# mapleSDuino-V0_1_012-eagle7.net
KiCad netlist of a schematic drawn in EAGLE
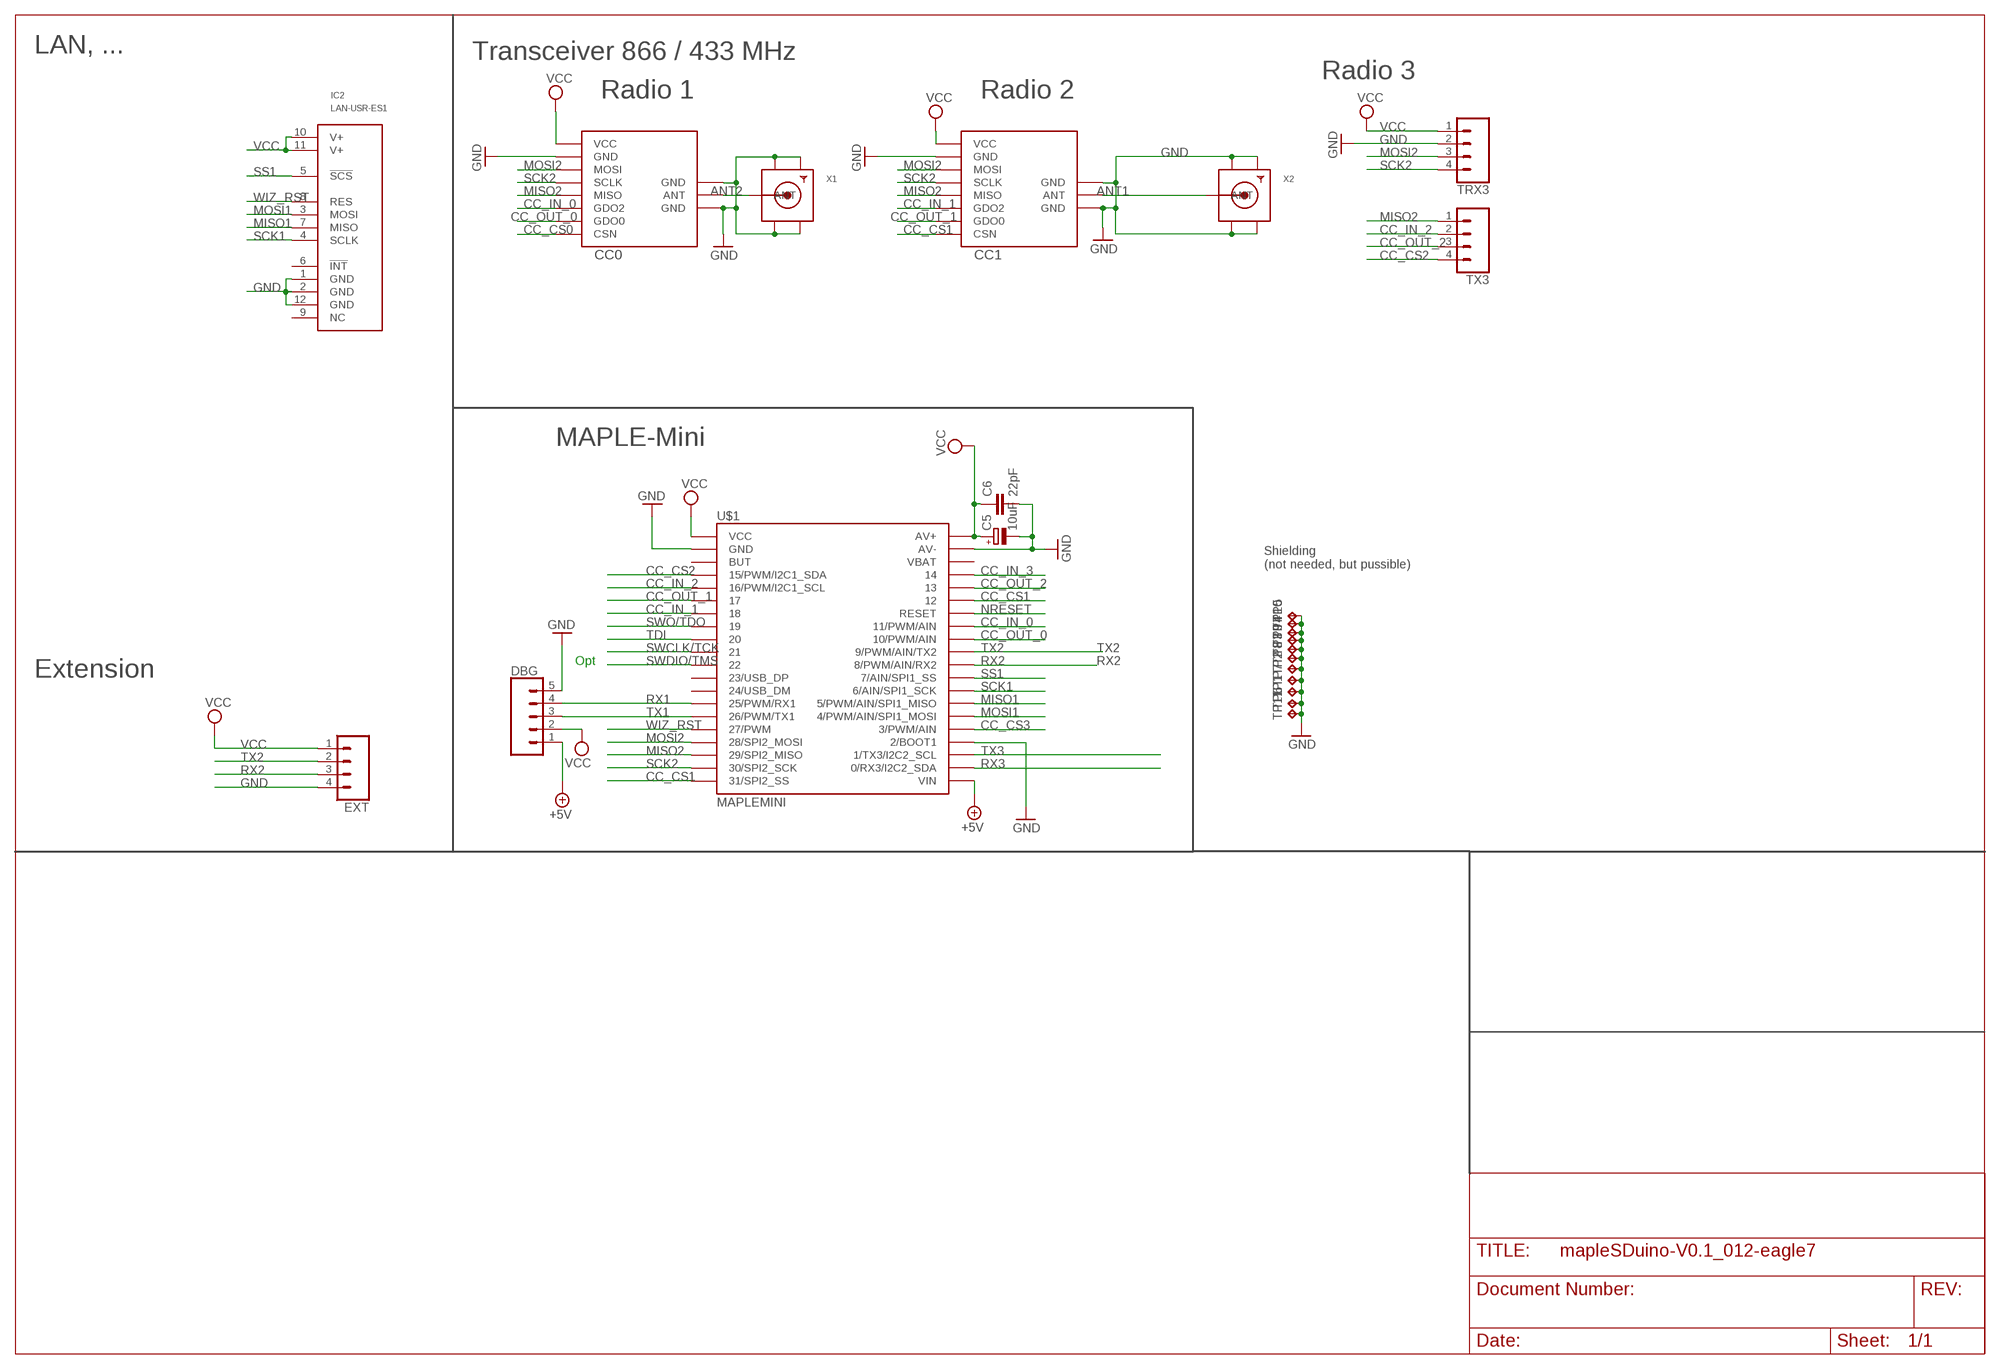
[diagram p0: schematic, sheet 1]

(export (version "E")
  (design (tool "Eeschema 10.0.6"))
  (components
    (comp (ref "C5")
      (value "10uF")
      (footprint "eagle-import:R_2012-12W")
      (libsource (lib "eagle-import") (part "CPOL-EUR/2012-12W"))
    )
    (comp (ref "C6")
      (value "22pF")
      (footprint "eagle-import:C0805")
      (libsource (lib "eagle-import") (part "C-EUC0805"))
    )
    (comp (ref "CC0")
      (value "CC1101")
      (footprint "eagle-import:CC1101_MODULE1_SMD")
      (libsource (lib "eagle-import") (part "CC1101_MODULE1SMD"))
    )
    (comp (ref "CC1")
      (value "CC1101_MODULE1SMD")
      (footprint "eagle-import:CC1101_MODULE1_SMD")
      (libsource (lib "eagle-import") (part "CC1101_MODULE1SMD"))
    )
    (comp (ref "DBG")
      (value "CONN_05LOCK")
      (footprint "eagle-import:1X05_LOCK")
      (libsource (lib "eagle-import") (part "CONN_05LOCK"))
    )
    (comp (ref "EXT")
      (value "CONN_04PTH")
      (footprint "eagle-import:1X04")
      (libsource (lib "eagle-import") (part "CONN_04PTH"))
    )
    (comp (ref "IC2")
      (value "LAN-USR-ES1")
      (footprint "eagle-import:USR-ES1")
      (libsource (lib "eagle-import") (part "LAN-USR-ES1"))
    )
    (comp (ref "TP1")
      (value "TPTP06SQ")
      (footprint "eagle-import:TP06SQ")
      (libsource (lib "eagle-import") (part "TPTP06SQ"))
    )
    (comp (ref "TP2")
      (value "TPTP06SQ")
      (footprint "eagle-import:TP06SQ")
      (libsource (lib "eagle-import") (part "TPTP06SQ"))
    )
    (comp (ref "TP3")
      (value "TPTP06SQ")
      (footprint "eagle-import:TP06SQ")
      (libsource (lib "eagle-import") (part "TPTP06SQ"))
    )
    (comp (ref "TP4")
      (value "TPTP06SQ")
      (footprint "eagle-import:TP06SQ")
      (libsource (lib "eagle-import") (part "TPTP06SQ"))
    )
    (comp (ref "TP5")
      (value "TPTP06SQ")
      (footprint "eagle-import:TP06SQ")
      (libsource (lib "eagle-import") (part "TPTP06SQ"))
    )
    (comp (ref "TP6")
      (value "TPTP06SQ")
      (footprint "eagle-import:TP06SQ")
      (libsource (lib "eagle-import") (part "TPTP06SQ"))
    )
    (comp (ref "TP7")
      (value "TPTP06SQ")
      (footprint "eagle-import:TP06SQ")
      (libsource (lib "eagle-import") (part "TPTP06SQ"))
    )
    (comp (ref "TP8")
      (value "TPTP06SQ")
      (footprint "eagle-import:TP06SQ")
      (libsource (lib "eagle-import") (part "TPTP06SQ"))
    )
    (comp (ref "TP9")
      (value "TPTP06SQ")
      (footprint "eagle-import:TP06SQ")
      (libsource (lib "eagle-import") (part "TPTP06SQ"))
    )
    (comp (ref "TP10")
      (value "TPTP06SQ")
      (footprint "eagle-import:TP06SQ")
      (libsource (lib "eagle-import") (part "TPTP06SQ"))
    )
    (comp (ref "TP11")
      (value "TPTP06SQ")
      (footprint "eagle-import:TP06SQ")
      (libsource (lib "eagle-import") (part "TPTP06SQ"))
    )
    (comp (ref "TRX3")
      (value "CONN_04PTH")
      (footprint "eagle-import:1X04")
      (libsource (lib "eagle-import") (part "CONN_04PTH"))
    )
    (comp (ref "TX3")
      (value "CONN_04PTH")
      (footprint "eagle-import:1X04")
      (libsource (lib "eagle-import") (part "CONN_04PTH"))
    )
    (comp (ref "U$1")
      (value "MAPLEMINI")
      (footprint "eagle-import:20-DIP")
      (libsource (lib "eagle-import") (part "MAPLEMINI"))
    )
    (comp (ref "X1")
      (value "SMACONNECTOR_EDGE")
      (footprint "eagle-import:SMA_EDGELAUNCH")
      (libsource (lib "eagle-import") (part "SMACONNECTOR_EDGE"))
    )
    (comp (ref "X2")
      (value "SMACONNECTOR_EDGE")
      (footprint "eagle-import:SMA_EDGELAUNCH")
      (libsource (lib "eagle-import") (part "SMACONNECTOR_EDGE"))
    )
  )
  (nets
    (net (code "1") (name "+5V") (class "Default")
      (node (ref "DBG") (pin "1") (pinfunction "1_1") (pintype "passive"))
      (node (ref "U$1") (pin "21") (pinfunction "VIN_21") (pintype "bidirectional"))
    )
    (net (code "2") (name "/ANT1") (class "Default")
      (node (ref "CC1") (pin "ANT") (pinfunction "ANT_ANT") (pintype "output"))
      (node (ref "X2") (pin "P") (pinfunction "ANT_P") (pintype "bidirectional"))
    )
    (net (code "3") (name "/ANT2") (class "Default")
      (node (ref "CC0") (pin "ANT") (pinfunction "ANT_ANT") (pintype "output"))
      (node (ref "X1") (pin "P") (pinfunction "ANT_P") (pintype "bidirectional"))
    )
    (net (code "4") (name "/CC_CS0") (class "Default")
      (node (ref "CC0") (pin "CSN") (pinfunction "CSN_CSN") (pintype "bidirectional"))
    )
    (net (code "5") (name "/CC_CS1") (class "Default")
      (node (ref "CC1") (pin "CSN") (pinfunction "CSN_CSN") (pintype "bidirectional"))
      (node (ref "U$1") (pin "20") (pinfunction "31/SPI2_SS_20") (pintype "bidirectional"))
      (node (ref "U$1") (pin "35") (pinfunction "12_35") (pintype "bidirectional"))
    )
    (net (code "6") (name "/CC_CS2") (class "Default")
      (node (ref "TX3") (pin "4") (pinfunction "4_4") (pintype "passive"))
      (node (ref "U$1") (pin "4") (pinfunction "15/PWM/I2C1_SDA_4") (pintype "bidirectional"))
    )
    (net (code "7") (name "/CC_CS3") (class "Default")
      (node (ref "U$1") (pin "25") (pinfunction "3/PWM/AIN_25") (pintype "bidirectional"))
    )
    (net (code "8") (name "/CC_IN_0") (class "Default")
      (node (ref "CC0") (pin "GDO2") (pinfunction "GDO2_GDO2") (pintype "bidirectional"))
      (node (ref "U$1") (pin "33") (pinfunction "11/PWM/AIN_33") (pintype "bidirectional"))
    )
    (net (code "9") (name "/CC_IN_1") (class "Default")
      (node (ref "CC1") (pin "GDO2") (pinfunction "GDO2_GDO2") (pintype "bidirectional"))
      (node (ref "U$1") (pin "7") (pinfunction "18_7") (pintype "bidirectional"))
    )
    (net (code "10") (name "/CC_IN_2") (class "Default")
      (node (ref "TX3") (pin "2") (pinfunction "2_2") (pintype "passive"))
      (node (ref "U$1") (pin "5") (pinfunction "16/PWM/I2C1_SCL_5") (pintype "bidirectional"))
    )
    (net (code "11") (name "/CC_IN_3") (class "Default")
      (node (ref "U$1") (pin "37") (pinfunction "14_37") (pintype "bidirectional"))
    )
    (net (code "12") (name "/CC_OUT_0") (class "Default")
      (node (ref "CC0") (pin "GDO0") (pinfunction "GDO0_GDO0") (pintype "bidirectional"))
      (node (ref "U$1") (pin "32") (pinfunction "10/PWM/AIN_32") (pintype "bidirectional"))
    )
    (net (code "13") (name "/CC_OUT_1") (class "Default")
      (node (ref "CC1") (pin "GDO0") (pinfunction "GDO0_GDO0") (pintype "bidirectional"))
      (node (ref "U$1") (pin "6") (pinfunction "17_6") (pintype "bidirectional"))
    )
    (net (code "14") (name "/CC_OUT_2") (class "Default")
      (node (ref "TX3") (pin "3") (pinfunction "3_3") (pintype "passive"))
      (node (ref "U$1") (pin "36") (pinfunction "13_36") (pintype "bidirectional"))
    )
    (net (code "15") (name "/MISO1") (class "Default")
      (node (ref "IC2") (pin "7") (pinfunction "MISO_7") (pintype "bidirectional"))
      (node (ref "U$1") (pin "27") (pinfunction "5/PWM/AIN/SPI1_MISO_27") (pintype "bidirectional"))
    )
    (net (code "16") (name "/MISO2") (class "Default")
      (node (ref "CC0") (pin "MISO") (pinfunction "MISO_MISO") (pintype "bidirectional"))
      (node (ref "CC1") (pin "MISO") (pinfunction "MISO_MISO") (pintype "bidirectional"))
      (node (ref "TX3") (pin "1") (pinfunction "1_1") (pintype "passive"))
      (node (ref "U$1") (pin "18") (pinfunction "29/SPI2_MISO_18") (pintype "bidirectional"))
    )
    (net (code "17") (name "/MOSI1") (class "Default")
      (node (ref "IC2") (pin "3") (pinfunction "MOSI_3") (pintype "bidirectional"))
      (node (ref "U$1") (pin "26") (pinfunction "4/PWM/AIN/SPI1_MOSI_26") (pintype "bidirectional"))
    )
    (net (code "18") (name "/MOSI2") (class "Default")
      (node (ref "CC0") (pin "MOSI") (pinfunction "MOSI_MOSI") (pintype "bidirectional"))
      (node (ref "CC1") (pin "MOSI") (pinfunction "MOSI_MOSI") (pintype "bidirectional"))
      (node (ref "TRX3") (pin "3") (pinfunction "3_3") (pintype "passive"))
      (node (ref "U$1") (pin "17") (pinfunction "28/SPI2_MOSI_17") (pintype "bidirectional"))
    )
    (net (code "19") (name "/NRESET") (class "Default")
      (node (ref "U$1") (pin "34") (pinfunction "RESET_34") (pintype "bidirectional"))
    )
    (net (code "20") (name "/RX1") (class "Default")
      (node (ref "DBG") (pin "4") (pinfunction "4_4") (pintype "passive"))
      (node (ref "U$1") (pin "14") (pinfunction "25/PWM/RX1_14") (pintype "bidirectional"))
    )
    (net (code "21") (name "/RX2") (class "Default")
      (node (ref "EXT") (pin "3") (pinfunction "3_3") (pintype "passive"))
      (node (ref "U$1") (pin "30") (pinfunction "8/PWM/AIN/RX2_30") (pintype "bidirectional"))
    )
    (net (code "22") (name "/RX3") (class "Default")
      (node (ref "U$1") (pin "22") (pinfunction "0/RX3/I2C2_SDA_22") (pintype "bidirectional"))
    )
    (net (code "23") (name "/SCK1") (class "Default")
      (node (ref "IC2") (pin "4") (pinfunction "SCLK_4") (pintype "input"))
      (node (ref "U$1") (pin "28") (pinfunction "6/AIN/SPI1_SCK_28") (pintype "bidirectional"))
    )
    (net (code "24") (name "/SCK2") (class "Default")
      (node (ref "CC0") (pin "SCLK") (pinfunction "SCLK_SCLK") (pintype "bidirectional"))
      (node (ref "CC1") (pin "SCLK") (pinfunction "SCLK_SCLK") (pintype "bidirectional"))
      (node (ref "TRX3") (pin "4") (pinfunction "4_4") (pintype "passive"))
      (node (ref "U$1") (pin "19") (pinfunction "30/SPI2_SCK_19") (pintype "bidirectional"))
    )
    (net (code "25") (name "/SS1") (class "Default")
      (node (ref "IC2") (pin "5") (pinfunction "~{SCS}_5") (pintype "input"))
      (node (ref "U$1") (pin "29") (pinfunction "7/AIN/SPI1_SS_29") (pintype "bidirectional"))
    )
    (net (code "26") (name "/SWCLK{slash}TCK") (class "Default")
      (node (ref "U$1") (pin "10") (pinfunction "21_10") (pintype "bidirectional"))
    )
    (net (code "27") (name "/SWDIO{slash}TMS") (class "Default")
      (node (ref "U$1") (pin "11") (pinfunction "22_11") (pintype "bidirectional"))
    )
    (net (code "28") (name "/SWO{slash}TDO") (class "Default")
      (node (ref "U$1") (pin "8") (pinfunction "19_8") (pintype "bidirectional"))
    )
    (net (code "29") (name "/TDI") (class "Default")
      (node (ref "U$1") (pin "9") (pinfunction "20_9") (pintype "bidirectional"))
    )
    (net (code "30") (name "/TX1") (class "Default")
      (node (ref "DBG") (pin "3") (pinfunction "3_3") (pintype "passive"))
      (node (ref "U$1") (pin "15") (pinfunction "26/PWM/TX1_15") (pintype "bidirectional"))
    )
    (net (code "31") (name "/TX2") (class "Default")
      (node (ref "EXT") (pin "2") (pinfunction "2_2") (pintype "passive"))
      (node (ref "U$1") (pin "31") (pinfunction "9/PWM/AIN/TX2_31") (pintype "bidirectional"))
    )
    (net (code "32") (name "/TX3") (class "Default")
      (node (ref "U$1") (pin "23") (pinfunction "1/TX3/I2C2_SCL_23") (pintype "bidirectional"))
    )
    (net (code "33") (name "/WIZ_RST") (class "Default")
      (node (ref "IC2") (pin "8") (pinfunction "RES_8") (pintype "input"))
      (node (ref "U$1") (pin "16") (pinfunction "27/PWM_16") (pintype "bidirectional"))
    )
    (net (code "34") (name "GND") (class "Default")
      (node (ref "C5") (pin "-") (pinfunction "-_-") (pintype "passive"))
      (node (ref "C6") (pin "2") (pinfunction "2_2") (pintype "passive"))
      (node (ref "CC0") (pin "GND@0") (pinfunction "GND_GND@0") (pintype "power_in"))
      (node (ref "CC0") (pin "GND@1") (pinfunction "GND_GND@1") (pintype "power_in"))
      (node (ref "CC0") (pin "GND@2") (pinfunction "GND_GND@2") (pintype "power_in"))
      (node (ref "CC1") (pin "GND@0") (pinfunction "GND_GND@0") (pintype "power_in"))
      (node (ref "CC1") (pin "GND@1") (pinfunction "GND_GND@1") (pintype "power_in"))
      (node (ref "CC1") (pin "GND@2") (pinfunction "GND_GND@2") (pintype "power_in"))
      (node (ref "DBG") (pin "5") (pinfunction "5_5") (pintype "passive"))
      (node (ref "EXT") (pin "4") (pinfunction "4_4") (pintype "passive"))
      (node (ref "IC2") (pin "1") (pinfunction "GND_1") (pintype "power_in"))
      (node (ref "IC2") (pin "12") (pinfunction "GND_12") (pintype "power_in"))
      (node (ref "IC2") (pin "2") (pinfunction "GND_2") (pintype "power_in"))
      (node (ref "TP1") (pin "TP") (pinfunction "TP_TP") (pintype "input"))
      (node (ref "TP10") (pin "TP") (pinfunction "TP_TP") (pintype "input"))
      (node (ref "TP11") (pin "TP") (pinfunction "TP_TP") (pintype "input"))
      (node (ref "TP2") (pin "TP") (pinfunction "TP_TP") (pintype "input"))
      (node (ref "TP3") (pin "TP") (pinfunction "TP_TP") (pintype "input"))
      (node (ref "TP4") (pin "TP") (pinfunction "TP_TP") (pintype "input"))
      (node (ref "TP5") (pin "TP") (pinfunction "TP_TP") (pintype "input"))
      (node (ref "TP6") (pin "TP") (pinfunction "TP_TP") (pintype "input"))
      (node (ref "TP7") (pin "TP") (pinfunction "TP_TP") (pintype "input"))
      (node (ref "TP8") (pin "TP") (pinfunction "TP_TP") (pintype "input"))
      (node (ref "TP9") (pin "TP") (pinfunction "TP_TP") (pintype "input"))
      (node (ref "TRX3") (pin "2") (pinfunction "2_2") (pintype "passive"))
      (node (ref "U$1") (pin "2") (pinfunction "GND_2") (pintype "bidirectional"))
      (node (ref "U$1") (pin "24") (pinfunction "2/BOOT1_24") (pintype "bidirectional"))
      (node (ref "U$1") (pin "39") (pinfunction "AV-_39") (pintype "bidirectional"))
      (node (ref "X1") (pin "GND@1") (pinfunction "GND4_GND@1") (pintype "power_in"))
      (node (ref "X1") (pin "GND@2") (pinfunction "GND3_GND@2") (pintype "power_in"))
      (node (ref "X1") (pin "GND@3") (pinfunction "GND2_GND@3") (pintype "power_in"))
      (node (ref "X1") (pin "GND@4") (pinfunction "GND1_GND@4") (pintype "power_in"))
      (node (ref "X2") (pin "GND@1") (pinfunction "GND4_GND@1") (pintype "power_in"))
      (node (ref "X2") (pin "GND@2") (pinfunction "GND3_GND@2") (pintype "power_in"))
      (node (ref "X2") (pin "GND@3") (pinfunction "GND2_GND@3") (pintype "power_in"))
      (node (ref "X2") (pin "GND@4") (pinfunction "GND1_GND@4") (pintype "power_in"))
    )
    (net (code "35") (name "VCC") (class "Default")
      (node (ref "C5") (pin "+") (pinfunction "+_+") (pintype "passive"))
      (node (ref "C6") (pin "1") (pinfunction "1_1") (pintype "passive"))
      (node (ref "CC0") (pin "VCC") (pinfunction "VCC_VCC") (pintype "power_in"))
      (node (ref "CC1") (pin "VCC") (pinfunction "VCC_VCC") (pintype "power_in"))
      (node (ref "DBG") (pin "2") (pinfunction "2_2") (pintype "passive"))
      (node (ref "EXT") (pin "1") (pinfunction "1_1") (pintype "passive"))
      (node (ref "IC2") (pin "10") (pinfunction "V+_10") (pintype "power_in"))
      (node (ref "IC2") (pin "11") (pinfunction "V+_11") (pintype "power_in"))
      (node (ref "TRX3") (pin "1") (pinfunction "1_1") (pintype "passive"))
      (node (ref "U$1") (pin "1") (pinfunction "VCC_1") (pintype "bidirectional"))
      (node (ref "U$1") (pin "40") (pinfunction "AV+_40") (pintype "bidirectional"))
    )
    (net (code "36") (name "unconnected-(IC2-NC-Pad9)") (class "Default")
      (node (ref "IC2") (pin "9") (pinfunction "NC_9") (pintype "no_connect"))
    )
    (net (code "37") (name "unconnected-(IC2-~{INT}-Pad6)") (class "Default")
      (node (ref "IC2") (pin "6") (pinfunction "~{INT}_6") (pintype "output"))
    )
    (net (code "38") (name "unconnected-(U$1-23{slash}USB_DP-Pad12)") (class "Default")
      (node (ref "U$1") (pin "12") (pinfunction "23/USB_DP_12") (pintype "bidirectional"))
    )
    (net (code "39") (name "unconnected-(U$1-24{slash}USB_DM-Pad13)") (class "Default")
      (node (ref "U$1") (pin "13") (pinfunction "24/USB_DM_13") (pintype "bidirectional"))
    )
    (net (code "40") (name "unconnected-(U$1-BUT-Pad3)") (class "Default")
      (node (ref "U$1") (pin "3") (pinfunction "BUT_3") (pintype "bidirectional"))
    )
    (net (code "41") (name "unconnected-(U$1-VBAT-Pad38)") (class "Default")
      (node (ref "U$1") (pin "38") (pinfunction "VBAT_38") (pintype "bidirectional"))
    )
  )
)
